# schem.net
KiCad netlist of a schematic drawn in EasyEDA
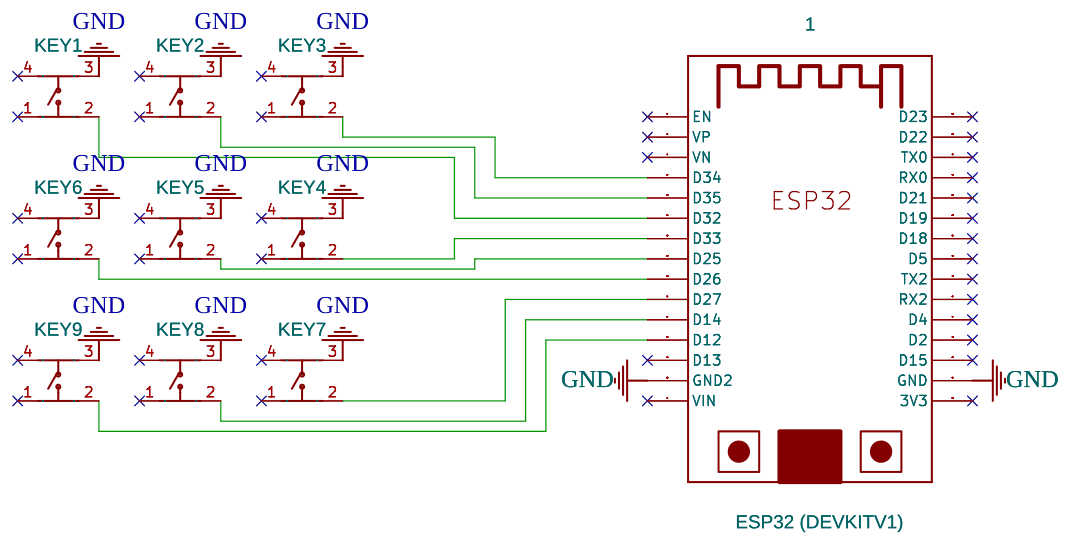
[diagram p0: schematic sheet]

(export (version "E")
  (design (tool "Eeschema 10.0.6"))
  (components
    (comp (ref "1") (value "ESP32 (DEVKITV1)") (libsource (lib "") (part "ESP32-DEVKIT-V1-30PIN")))
    (comp (ref "KEY1")
      (value "K2-1841SP")
      (fields (field (name "Manufacturer Part") "K2-1841SP-H4SW-02") (field (name "Manufacturer") "韩国韩荣"))
      (libsource (lib "") (part "K2-1841SP"))
    )
    (comp (ref "KEY2")
      (value "K2-1841SP")
      (fields (field (name "Manufacturer Part") "K2-1841SP-H4SW-02") (field (name "Manufacturer") "韩国韩荣"))
      (libsource (lib "") (part "K2-1841SP"))
    )
    (comp (ref "KEY3")
      (value "K2-1841SP")
      (fields (field (name "Manufacturer Part") "K2-1841SP-H4SW-02") (field (name "Manufacturer") "韩国韩荣"))
      (libsource (lib "") (part "K2-1841SP"))
    )
    (comp (ref "KEY4")
      (value "K2-1841SP")
      (fields (field (name "Manufacturer Part") "K2-1841SP-H4SW-02") (field (name "Manufacturer") "韩国韩荣"))
      (libsource (lib "") (part "K2-1841SP"))
    )
    (comp (ref "KEY5")
      (value "K2-1841SP")
      (fields (field (name "Manufacturer Part") "K2-1841SP-H4SW-02") (field (name "Manufacturer") "韩国韩荣"))
      (libsource (lib "") (part "K2-1841SP"))
    )
    (comp (ref "KEY6")
      (value "K2-1841SP")
      (fields (field (name "Manufacturer Part") "K2-1841SP-H4SW-02") (field (name "Manufacturer") "韩国韩荣"))
      (libsource (lib "") (part "K2-1841SP"))
    )
    (comp (ref "KEY7")
      (value "K2-1841SP")
      (fields (field (name "Manufacturer Part") "K2-1841SP-H4SW-02") (field (name "Manufacturer") "韩国韩荣"))
      (libsource (lib "") (part "K2-1841SP"))
    )
    (comp (ref "KEY8")
      (value "K2-1841SP")
      (fields (field (name "Manufacturer Part") "K2-1841SP-H4SW-02") (field (name "Manufacturer") "韩国韩荣"))
      (libsource (lib "") (part "K2-1841SP"))
    )
    (comp (ref "KEY9")
      (value "K2-1841SP")
      (fields (field (name "Manufacturer Part") "K2-1841SP-H4SW-02") (field (name "Manufacturer") "韩国韩荣"))
      (libsource (lib "") (part "K2-1841SP"))
    )
  )
  (nets
    (net (code "1") (name "GND") (class "Default")
      (node (ref "1") (pin "GND") (pinfunction "GND_GND") (pintype "unspecified"))
      (node (ref "1") (pin "GND2") (pinfunction "GND2_GND2") (pintype "unspecified"))
      (node (ref "KEY1") (pin "3") (pinfunction "3_3") (pintype "unspecified"))
      (node (ref "KEY2") (pin "3") (pinfunction "3_3") (pintype "unspecified"))
      (node (ref "KEY3") (pin "3") (pinfunction "3_3") (pintype "unspecified"))
      (node (ref "KEY4") (pin "3") (pinfunction "3_3") (pintype "unspecified"))
      (node (ref "KEY5") (pin "3") (pinfunction "3_3") (pintype "unspecified"))
      (node (ref "KEY6") (pin "3") (pinfunction "3_3") (pintype "unspecified"))
      (node (ref "KEY7") (pin "3") (pinfunction "3_3") (pintype "unspecified"))
      (node (ref "KEY8") (pin "3") (pinfunction "3_3") (pintype "unspecified"))
      (node (ref "KEY9") (pin "3") (pinfunction "3_3") (pintype "unspecified"))
    )
    (net (code "2") (name "Net-(1-PadD12)") (class "Default")
      (node (ref "1") (pin "D12") (pinfunction "D12_D12") (pintype "unspecified"))
      (node (ref "KEY9") (pin "2") (pinfunction "2_2") (pintype "unspecified"))
    )
    (net (code "3") (name "Net-(1-PadD14)") (class "Default")
      (node (ref "1") (pin "D14") (pinfunction "D14_D14") (pintype "unspecified"))
      (node (ref "KEY8") (pin "2") (pinfunction "2_2") (pintype "unspecified"))
    )
    (net (code "4") (name "Net-(1-PadD25)") (class "Default")
      (node (ref "1") (pin "D25") (pinfunction "D25_D25") (pintype "unspecified"))
      (node (ref "KEY5") (pin "2") (pinfunction "2_2") (pintype "unspecified"))
    )
    (net (code "5") (name "Net-(1-PadD26)") (class "Default")
      (node (ref "1") (pin "D26") (pinfunction "D26_D26") (pintype "unspecified"))
      (node (ref "KEY6") (pin "2") (pinfunction "2_2") (pintype "unspecified"))
    )
    (net (code "6") (name "Net-(1-PadD27)") (class "Default")
      (node (ref "1") (pin "D27") (pinfunction "D27_D27") (pintype "unspecified"))
      (node (ref "KEY7") (pin "2") (pinfunction "2_2") (pintype "unspecified"))
    )
    (net (code "7") (name "Net-(1-PadD32)") (class "Default")
      (node (ref "1") (pin "D32") (pinfunction "D32_D32") (pintype "unspecified"))
      (node (ref "KEY1") (pin "2") (pinfunction "2_2") (pintype "unspecified"))
    )
    (net (code "8") (name "Net-(1-PadD33)") (class "Default")
      (node (ref "1") (pin "D33") (pinfunction "D33_D33") (pintype "unspecified"))
      (node (ref "KEY4") (pin "2") (pinfunction "2_2") (pintype "unspecified"))
    )
    (net (code "9") (name "Net-(1-PadD34)") (class "Default")
      (node (ref "1") (pin "D34") (pinfunction "D34_D34") (pintype "unspecified"))
      (node (ref "KEY3") (pin "2") (pinfunction "2_2") (pintype "unspecified"))
    )
    (net (code "10") (name "Net-(1-PadD35)") (class "Default")
      (node (ref "1") (pin "D35") (pinfunction "D35_D35") (pintype "unspecified"))
      (node (ref "KEY2") (pin "2") (pinfunction "2_2") (pintype "unspecified"))
    )
    (net (code "11") (name "unconnected-(1-Pad3V3)") (class "Default")
      (node (ref "1") (pin "3V3") (pinfunction "3V3_3V3") (pintype "unspecified+no_connect"))
    )
    (net (code "12") (name "unconnected-(1-PadD2)") (class "Default")
      (node (ref "1") (pin "D2") (pinfunction "D2_D2") (pintype "unspecified+no_connect"))
    )
    (net (code "13") (name "unconnected-(1-PadD4)") (class "Default")
      (node (ref "1") (pin "D4") (pinfunction "D4_D4") (pintype "unspecified+no_connect"))
    )
    (net (code "14") (name "unconnected-(1-PadD5)") (class "Default")
      (node (ref "1") (pin "D5") (pinfunction "D5_D5") (pintype "unspecified+no_connect"))
    )
    (net (code "15") (name "unconnected-(1-PadD13)") (class "Default")
      (node (ref "1") (pin "D13") (pinfunction "D13_D13") (pintype "unspecified+no_connect"))
    )
    (net (code "16") (name "unconnected-(1-PadD15)") (class "Default")
      (node (ref "1") (pin "D15") (pinfunction "D15_D15") (pintype "unspecified+no_connect"))
    )
    (net (code "17") (name "unconnected-(1-PadD18)") (class "Default")
      (node (ref "1") (pin "D18") (pinfunction "D18_D18") (pintype "unspecified+no_connect"))
    )
    (net (code "18") (name "unconnected-(1-PadD19)") (class "Default")
      (node (ref "1") (pin "D19") (pinfunction "D19_D19") (pintype "unspecified+no_connect"))
    )
    (net (code "19") (name "unconnected-(1-PadD21)") (class "Default")
      (node (ref "1") (pin "D21") (pinfunction "D21_D21") (pintype "unspecified+no_connect"))
    )
    (net (code "20") (name "unconnected-(1-PadD22)") (class "Default")
      (node (ref "1") (pin "D22") (pinfunction "D22_D22") (pintype "unspecified+no_connect"))
    )
    (net (code "21") (name "unconnected-(1-PadD23)") (class "Default")
      (node (ref "1") (pin "D23") (pinfunction "D23_D23") (pintype "unspecified+no_connect"))
    )
    (net (code "22") (name "unconnected-(1-PadEN)") (class "Default")
      (node (ref "1") (pin "EN") (pinfunction "EN_EN") (pintype "unspecified+no_connect"))
    )
    (net (code "23") (name "unconnected-(1-PadRX0)") (class "Default")
      (node (ref "1") (pin "RX0") (pinfunction "RX0_RX0") (pintype "unspecified+no_connect"))
    )
    (net (code "24") (name "unconnected-(1-PadRX2)") (class "Default")
      (node (ref "1") (pin "RX2") (pinfunction "RX2_RX2") (pintype "unspecified+no_connect"))
    )
    (net (code "25") (name "unconnected-(1-PadTX0)") (class "Default")
      (node (ref "1") (pin "TX0") (pinfunction "TX0_TX0") (pintype "unspecified+no_connect"))
    )
    (net (code "26") (name "unconnected-(1-PadTX2)") (class "Default")
      (node (ref "1") (pin "TX2") (pinfunction "TX2_TX2") (pintype "unspecified+no_connect"))
    )
    (net (code "27") (name "unconnected-(1-PadVIN)") (class "Default")
      (node (ref "1") (pin "VIN") (pinfunction "VIN_VIN") (pintype "unspecified+no_connect"))
    )
    (net (code "28") (name "unconnected-(1-PadVN)") (class "Default")
      (node (ref "1") (pin "VN") (pinfunction "VN_VN") (pintype "unspecified+no_connect"))
    )
    (net (code "29") (name "unconnected-(1-PadVP)") (class "Default")
      (node (ref "1") (pin "VP") (pinfunction "VP_VP") (pintype "unspecified+no_connect"))
    )
    (net (code "30") (name "unconnected-(KEY1-Pad1)") (class "Default")
      (node (ref "KEY1") (pin "1") (pinfunction "1_1") (pintype "unspecified+no_connect"))
    )
    (net (code "31") (name "unconnected-(KEY1-Pad4)") (class "Default")
      (node (ref "KEY1") (pin "4") (pinfunction "4_4") (pintype "unspecified+no_connect"))
    )
    (net (code "32") (name "unconnected-(KEY2-Pad1)") (class "Default")
      (node (ref "KEY2") (pin "1") (pinfunction "1_1") (pintype "unspecified+no_connect"))
    )
    (net (code "33") (name "unconnected-(KEY2-Pad4)") (class "Default")
      (node (ref "KEY2") (pin "4") (pinfunction "4_4") (pintype "unspecified+no_connect"))
    )
    (net (code "34") (name "unconnected-(KEY3-Pad1)") (class "Default")
      (node (ref "KEY3") (pin "1") (pinfunction "1_1") (pintype "unspecified+no_connect"))
    )
    (net (code "35") (name "unconnected-(KEY3-Pad4)") (class "Default")
      (node (ref "KEY3") (pin "4") (pinfunction "4_4") (pintype "unspecified+no_connect"))
    )
    (net (code "36") (name "unconnected-(KEY4-Pad1)") (class "Default")
      (node (ref "KEY4") (pin "1") (pinfunction "1_1") (pintype "unspecified+no_connect"))
    )
    (net (code "37") (name "unconnected-(KEY4-Pad4)") (class "Default")
      (node (ref "KEY4") (pin "4") (pinfunction "4_4") (pintype "unspecified+no_connect"))
    )
    (net (code "38") (name "unconnected-(KEY5-Pad1)") (class "Default")
      (node (ref "KEY5") (pin "1") (pinfunction "1_1") (pintype "unspecified+no_connect"))
    )
    (net (code "39") (name "unconnected-(KEY5-Pad4)") (class "Default")
      (node (ref "KEY5") (pin "4") (pinfunction "4_4") (pintype "unspecified+no_connect"))
    )
    (net (code "40") (name "unconnected-(KEY6-Pad1)") (class "Default")
      (node (ref "KEY6") (pin "1") (pinfunction "1_1") (pintype "unspecified+no_connect"))
    )
    (net (code "41") (name "unconnected-(KEY6-Pad4)") (class "Default")
      (node (ref "KEY6") (pin "4") (pinfunction "4_4") (pintype "unspecified+no_connect"))
    )
    (net (code "42") (name "unconnected-(KEY7-Pad1)") (class "Default")
      (node (ref "KEY7") (pin "1") (pinfunction "1_1") (pintype "unspecified+no_connect"))
    )
    (net (code "43") (name "unconnected-(KEY7-Pad4)") (class "Default")
      (node (ref "KEY7") (pin "4") (pinfunction "4_4") (pintype "unspecified+no_connect"))
    )
    (net (code "44") (name "unconnected-(KEY8-Pad1)") (class "Default")
      (node (ref "KEY8") (pin "1") (pinfunction "1_1") (pintype "unspecified+no_connect"))
    )
    (net (code "45") (name "unconnected-(KEY8-Pad4)") (class "Default")
      (node (ref "KEY8") (pin "4") (pinfunction "4_4") (pintype "unspecified+no_connect"))
    )
    (net (code "46") (name "unconnected-(KEY9-Pad1)") (class "Default")
      (node (ref "KEY9") (pin "1") (pinfunction "1_1") (pintype "unspecified+no_connect"))
    )
    (net (code "47") (name "unconnected-(KEY9-Pad4)") (class "Default")
      (node (ref "KEY9") (pin "4") (pinfunction "4_4") (pintype "unspecified+no_connect"))
    )
  )
)
